# Balanza.net
KiCad netlist of a schematic drawn in Altium Designer
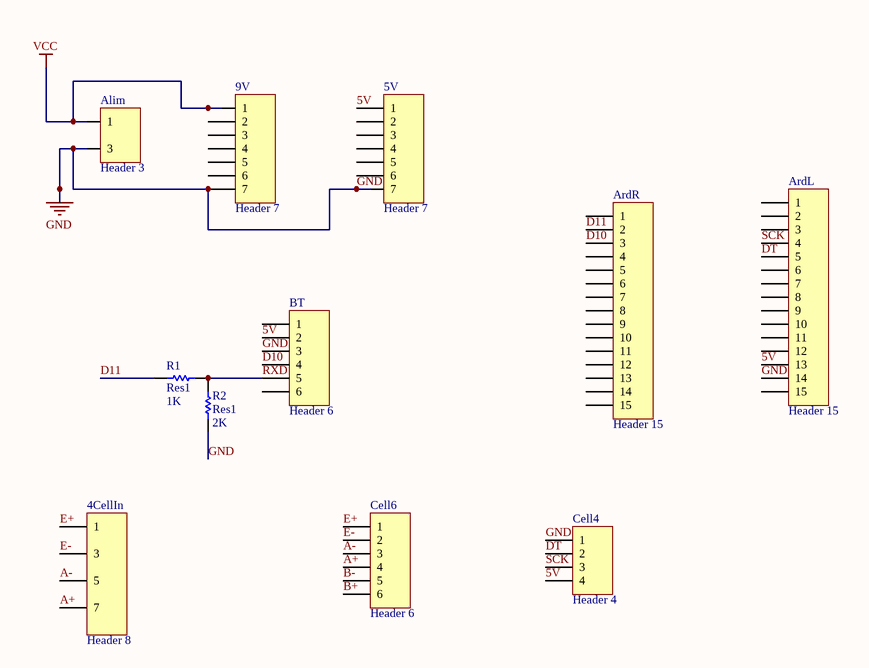
[diagram p0: Balanza.SchDoc]

(export (version "E")
  (design (tool "Eeschema 10.0.6"))
  (components
    (comp (ref "4CellIn")
      (value "Header 8")
      (footprint "HDR1X8")
      (description "Header, 8-Pin")
      (fields (field (name "PUBLISHER") "Altium Limited"))
      (libsource (lib "Miscellaneous Connectors") (part "Header 8"))
    )
    (comp (ref "5V")
      (value "Header 7")
      (footprint "HDR1X7")
      (description "Header, 7-Pin")
      (fields (field (name "PUBLISHER") "Altium Limited"))
      (libsource (lib "Miscellaneous Connectors") (part "Header 7"))
    )
    (comp (ref "9V")
      (value "Header 7")
      (footprint "HDR1X7")
      (description "Header, 7-Pin")
      (fields (field (name "PUBLISHER") "Altium Limited"))
      (libsource (lib "Miscellaneous Connectors") (part "Header 7"))
    )
    (comp (ref "Alim")
      (value "Header 3")
      (footprint "HDR1X3")
      (description "Header, 3-Pin")
      (fields (field (name "PUBLISHER") "Altium Limited"))
      (libsource (lib "Miscellaneous Connectors") (part "Header 3"))
    )
    (comp (ref "ArdL")
      (value "Header 15")
      (footprint "HDR1X15")
      (description "Header, 15-Pin")
      (fields (field (name "PUBLISHER") "Altium Limited"))
      (libsource (lib "Miscellaneous Connectors") (part "Header 15"))
    )
    (comp (ref "ArdR")
      (value "Header 15")
      (footprint "HDR1X15")
      (description "Header, 15-Pin")
      (fields (field (name "PUBLISHER") "Altium Limited"))
      (libsource (lib "Miscellaneous Connectors") (part "Header 15"))
    )
    (comp (ref "BT")
      (value "Header 6")
      (footprint "HDR1X6")
      (description "Header, 6-Pin")
      (fields (field (name "PUBLISHER") "Altium Limited"))
      (libsource (lib "Miscellaneous Connectors") (part "Header 6"))
    )
    (comp (ref "Cell4")
      (value "Header 4")
      (footprint "HDR1X4")
      (description "Header, 4-Pin")
      (fields (field (name "PUBLISHER") "Altium Limited"))
      (libsource (lib "Miscellaneous Connectors") (part "Header 4"))
    )
    (comp (ref "Cell6")
      (value "Header 6")
      (footprint "HDR1X6")
      (description "Header, 6-Pin")
      (fields (field (name "PUBLISHER") "Altium Limited"))
      (libsource (lib "Miscellaneous Connectors") (part "Header 6"))
    )
    (comp (ref "R1")
      (value "Res1")
      (footprint "AXIAL-0.3")
      (description "Resistor")
      (fields (field (name "ALTIUM_VALUE") "1K") (field (name "PUBLISHER") "Altium Limited"))
      (libsource (lib "Miscellaneous Devices") (part "Res1"))
    )
    (comp (ref "R2")
      (value "Res1")
      (footprint "AXIAL-0.3")
      (description "Resistor")
      (fields (field (name "ALTIUM_VALUE") "2K") (field (name "PUBLISHER") "Altium Limited"))
      (libsource (lib "Miscellaneous Devices") (part "Res1"))
    )
  )
  (nets
    (net (code "1") (name "/5V") (class "Default")
      (node (ref "5V") (pin "1") (pinfunction "1_1") (pintype "passive"))
      (node (ref "ArdL") (pin "13") (pinfunction "13_13") (pintype "passive"))
      (node (ref "BT") (pin "2") (pinfunction "2_2") (pintype "passive"))
      (node (ref "Cell4") (pin "4") (pinfunction "4_4") (pintype "passive"))
    )
    (net (code "2") (name "/A+") (class "Default")
      (node (ref "4CellIn") (pin "7") (pinfunction "7_7") (pintype "passive"))
      (node (ref "Cell6") (pin "4") (pinfunction "4_4") (pintype "passive"))
    )
    (net (code "3") (name "/A-") (class "Default")
      (node (ref "4CellIn") (pin "5") (pinfunction "5_5") (pintype "passive"))
      (node (ref "Cell6") (pin "3") (pinfunction "3_3") (pintype "passive"))
    )
    (net (code "4") (name "/B+") (class "Default")
      (node (ref "Cell6") (pin "6") (pinfunction "6_6") (pintype "passive"))
    )
    (net (code "5") (name "/B-") (class "Default")
      (node (ref "Cell6") (pin "5") (pinfunction "5_5") (pintype "passive"))
    )
    (net (code "6") (name "/D10") (class "Default")
      (node (ref "ArdR") (pin "3") (pinfunction "3_3") (pintype "passive"))
      (node (ref "BT") (pin "4") (pinfunction "4_4") (pintype "passive"))
    )
    (net (code "7") (name "/D11") (class "Default")
      (node (ref "ArdR") (pin "2") (pinfunction "2_2") (pintype "passive"))
      (node (ref "R1") (pin "1") (pinfunction "1_1") (pintype "passive"))
    )
    (net (code "8") (name "/DT") (class "Default")
      (node (ref "ArdL") (pin "5") (pinfunction "5_5") (pintype "passive"))
      (node (ref "Cell4") (pin "2") (pinfunction "2_2") (pintype "passive"))
    )
    (net (code "9") (name "/E+") (class "Default")
      (node (ref "4CellIn") (pin "1") (pinfunction "1_1") (pintype "passive"))
      (node (ref "Cell6") (pin "1") (pinfunction "1_1") (pintype "passive"))
    )
    (net (code "10") (name "/E-") (class "Default")
      (node (ref "4CellIn") (pin "3") (pinfunction "3_3") (pintype "passive"))
      (node (ref "Cell6") (pin "2") (pinfunction "2_2") (pintype "passive"))
    )
    (net (code "11") (name "/RXD") (class "Default")
      (node (ref "BT") (pin "5") (pinfunction "5_5") (pintype "passive"))
      (node (ref "R1") (pin "2") (pinfunction "2_2") (pintype "passive"))
      (node (ref "R2") (pin "1") (pinfunction "1_1") (pintype "passive"))
    )
    (net (code "12") (name "/SCK") (class "Default")
      (node (ref "ArdL") (pin "4") (pinfunction "4_4") (pintype "passive"))
      (node (ref "Cell4") (pin "3") (pinfunction "3_3") (pintype "passive"))
    )
    (net (code "13") (name "GND") (class "Default")
      (node (ref "5V") (pin "7") (pinfunction "7_7") (pintype "passive"))
      (node (ref "9V") (pin "7") (pinfunction "7_7") (pintype "passive"))
      (node (ref "Alim") (pin "3") (pinfunction "3_3") (pintype "passive"))
      (node (ref "ArdL") (pin "14") (pinfunction "14_14") (pintype "passive"))
      (node (ref "BT") (pin "3") (pinfunction "3_3") (pintype "passive"))
      (node (ref "Cell4") (pin "1") (pinfunction "1_1") (pintype "passive"))
      (node (ref "R2") (pin "2") (pinfunction "2_2") (pintype "passive"))
    )
    (net (code "14") (name "VCC") (class "Default")
      (node (ref "9V") (pin "1") (pinfunction "1_1") (pintype "passive"))
      (node (ref "Alim") (pin "1") (pinfunction "1_1") (pintype "passive"))
    )
    (net (code "15") (name "unconnected-(5V-Pad2)") (class "Default")
      (node (ref "5V") (pin "2") (pinfunction "2_2") (pintype "passive"))
    )
    (net (code "16") (name "unconnected-(5V-Pad3)") (class "Default")
      (node (ref "5V") (pin "3") (pinfunction "3_3") (pintype "passive"))
    )
    (net (code "17") (name "unconnected-(5V-Pad4)") (class "Default")
      (node (ref "5V") (pin "4") (pinfunction "4_4") (pintype "passive"))
    )
    (net (code "18") (name "unconnected-(5V-Pad5)") (class "Default")
      (node (ref "5V") (pin "5") (pinfunction "5_5") (pintype "passive"))
    )
    (net (code "19") (name "unconnected-(5V-Pad6)") (class "Default")
      (node (ref "5V") (pin "6") (pinfunction "6_6") (pintype "passive"))
    )
    (net (code "20") (name "unconnected-(9V-Pad2)") (class "Default")
      (node (ref "9V") (pin "2") (pinfunction "2_2") (pintype "passive"))
    )
    (net (code "21") (name "unconnected-(9V-Pad3)") (class "Default")
      (node (ref "9V") (pin "3") (pinfunction "3_3") (pintype "passive"))
    )
    (net (code "22") (name "unconnected-(9V-Pad4)") (class "Default")
      (node (ref "9V") (pin "4") (pinfunction "4_4") (pintype "passive"))
    )
    (net (code "23") (name "unconnected-(9V-Pad5)") (class "Default")
      (node (ref "9V") (pin "5") (pinfunction "5_5") (pintype "passive"))
    )
    (net (code "24") (name "unconnected-(9V-Pad6)") (class "Default")
      (node (ref "9V") (pin "6") (pinfunction "6_6") (pintype "passive"))
    )
    (net (code "25") (name "unconnected-(ArdL-Pad1)") (class "Default")
      (node (ref "ArdL") (pin "1") (pinfunction "1_1") (pintype "passive"))
    )
    (net (code "26") (name "unconnected-(ArdL-Pad2)") (class "Default")
      (node (ref "ArdL") (pin "2") (pinfunction "2_2") (pintype "passive"))
    )
    (net (code "27") (name "unconnected-(ArdL-Pad3)") (class "Default")
      (node (ref "ArdL") (pin "3") (pinfunction "3_3") (pintype "passive"))
    )
    (net (code "28") (name "unconnected-(ArdL-Pad6)") (class "Default")
      (node (ref "ArdL") (pin "6") (pinfunction "6_6") (pintype "passive"))
    )
    (net (code "29") (name "unconnected-(ArdL-Pad7)") (class "Default")
      (node (ref "ArdL") (pin "7") (pinfunction "7_7") (pintype "passive"))
    )
    (net (code "30") (name "unconnected-(ArdL-Pad8)") (class "Default")
      (node (ref "ArdL") (pin "8") (pinfunction "8_8") (pintype "passive"))
    )
    (net (code "31") (name "unconnected-(ArdL-Pad9)") (class "Default")
      (node (ref "ArdL") (pin "9") (pinfunction "9_9") (pintype "passive"))
    )
    (net (code "32") (name "unconnected-(ArdL-Pad10)") (class "Default")
      (node (ref "ArdL") (pin "10") (pinfunction "10_10") (pintype "passive"))
    )
    (net (code "33") (name "unconnected-(ArdL-Pad11)") (class "Default")
      (node (ref "ArdL") (pin "11") (pinfunction "11_11") (pintype "passive"))
    )
    (net (code "34") (name "unconnected-(ArdL-Pad12)") (class "Default")
      (node (ref "ArdL") (pin "12") (pinfunction "12_12") (pintype "passive"))
    )
    (net (code "35") (name "unconnected-(ArdL-Pad15)") (class "Default")
      (node (ref "ArdL") (pin "15") (pinfunction "15_15") (pintype "passive"))
    )
    (net (code "36") (name "unconnected-(ArdR-Pad1)") (class "Default")
      (node (ref "ArdR") (pin "1") (pinfunction "1_1") (pintype "passive"))
    )
    (net (code "37") (name "unconnected-(ArdR-Pad4)") (class "Default")
      (node (ref "ArdR") (pin "4") (pinfunction "4_4") (pintype "passive"))
    )
    (net (code "38") (name "unconnected-(ArdR-Pad5)") (class "Default")
      (node (ref "ArdR") (pin "5") (pinfunction "5_5") (pintype "passive"))
    )
    (net (code "39") (name "unconnected-(ArdR-Pad6)") (class "Default")
      (node (ref "ArdR") (pin "6") (pinfunction "6_6") (pintype "passive"))
    )
    (net (code "40") (name "unconnected-(ArdR-Pad7)") (class "Default")
      (node (ref "ArdR") (pin "7") (pinfunction "7_7") (pintype "passive"))
    )
    (net (code "41") (name "unconnected-(ArdR-Pad8)") (class "Default")
      (node (ref "ArdR") (pin "8") (pinfunction "8_8") (pintype "passive"))
    )
    (net (code "42") (name "unconnected-(ArdR-Pad9)") (class "Default")
      (node (ref "ArdR") (pin "9") (pinfunction "9_9") (pintype "passive"))
    )
    (net (code "43") (name "unconnected-(ArdR-Pad10)") (class "Default")
      (node (ref "ArdR") (pin "10") (pinfunction "10_10") (pintype "passive"))
    )
    (net (code "44") (name "unconnected-(ArdR-Pad11)") (class "Default")
      (node (ref "ArdR") (pin "11") (pinfunction "11_11") (pintype "passive"))
    )
    (net (code "45") (name "unconnected-(ArdR-Pad12)") (class "Default")
      (node (ref "ArdR") (pin "12") (pinfunction "12_12") (pintype "passive"))
    )
    (net (code "46") (name "unconnected-(ArdR-Pad13)") (class "Default")
      (node (ref "ArdR") (pin "13") (pinfunction "13_13") (pintype "passive"))
    )
    (net (code "47") (name "unconnected-(ArdR-Pad14)") (class "Default")
      (node (ref "ArdR") (pin "14") (pinfunction "14_14") (pintype "passive"))
    )
    (net (code "48") (name "unconnected-(ArdR-Pad15)") (class "Default")
      (node (ref "ArdR") (pin "15") (pinfunction "15_15") (pintype "passive"))
    )
    (net (code "49") (name "unconnected-(BT-Pad1)") (class "Default")
      (node (ref "BT") (pin "1") (pinfunction "1_1") (pintype "passive"))
    )
    (net (code "50") (name "unconnected-(BT-Pad6)") (class "Default")
      (node (ref "BT") (pin "6") (pinfunction "6_6") (pintype "passive"))
    )
  )
)
